# Battery_Holder_VNA.net
KiCad netlist of a schematic drawn in Altium Designer
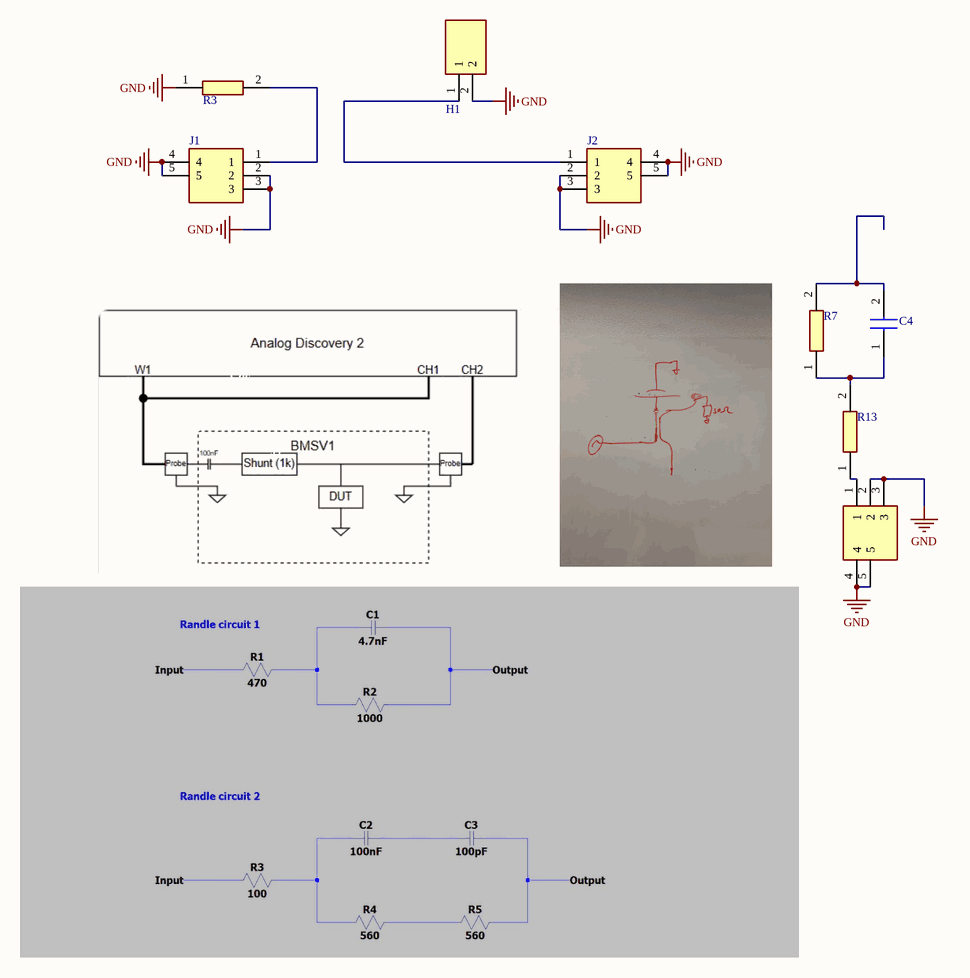
[diagram p0: Battery_Holder_VNA.SchDoc]

(export (version "E")
  (design (tool "Eeschema 10.0.6"))
  (components
    (comp (ref "C4")
      (value "200A472MT50XT")
      (footprint "SamacSys:CAPC1514X145N")
      (description "Capacitor")
      (libsource (lib "*") (part "200A472MT50XT"))
    )
    (comp (ref "H1")
      (value "1015")
      (footprint "SamacSys:1015")
      (description "Hardware")
      (fields (field (name "MOUSER PART NUMBER") "534-1015"))
      (libsource (lib "*") (part "1015"))
    )
    (comp (ref "J1")
      (value "60311002114501")
      (footprint "SamacSys:60311002114501")
      (description "Connector")
      (fields (field (name "MOUSER PART NUMBER") "710-60311002114501"))
      (libsource (lib "*") (part "60311002114501"))
    )
    (comp (ref "J2")
      (value "60311002114501")
      (footprint "SamacSys:60311002114501")
      (description "Connector")
      (fields (field (name "MOUSER PART NUMBER") "710-60311002114501"))
      (libsource (lib "") (part "60311002114501_2"))
    )
    (comp (ref "J3")
      (value "60311002114501")
      (footprint "SamacSys:60311002114501")
      (description "Connector")
      (fields (field (name "MOUSER PART NUMBER") "710-60311002114501"))
      (libsource (lib "") (part "60311002114501_1"))
    )
    (comp (ref "R3")
      (value "CH0402-50RGFT")
      (footprint "SamacSys:RESC1006X63N")
      (description "Resistor")
      (fields (field (name "MOUSER PART NUMBER") "71-CH0402-50RGFT"))
      (libsource (lib "*") (part "CH0402-50RGFT"))
    )
    (comp (ref "R7")
      (value "FC0402E1001DTT5")
      (footprint "SamacSys:RESC1106X42N")
      (description "Resistor")
      (fields (field (name "MOUSER PART NUMBER") "71-FC0402E1001DTT5"))
      (libsource (lib "*") (part "FC0402E1001DTT5"))
    )
    (comp (ref "R13")
      (value "CH0402-500RGFPT")
      (footprint "SamacSys:RESC1006X63N")
      (description "Resistor")
      (fields (field (name "MOUSER PART NUMBER") "71-CH0402-500RGFPT"))
      (libsource (lib "*") (part "CH0402-500RGFPT"))
    )
  )
  (nets
    (net (code "1") (name "GND") (class "Default")
      (node (ref "H1") (pin "2") (pinfunction "2_2") (pintype "passive"))
      (node (ref "J1") (pin "2") (pinfunction "2_2") (pintype "passive"))
      (node (ref "J1") (pin "3") (pinfunction "3_3") (pintype "passive"))
      (node (ref "J1") (pin "4") (pinfunction "4_4") (pintype "passive"))
      (node (ref "J1") (pin "5") (pinfunction "5_5") (pintype "passive"))
      (node (ref "J2") (pin "2") (pinfunction "2_2") (pintype "passive"))
      (node (ref "J2") (pin "3") (pinfunction "3_3") (pintype "passive"))
      (node (ref "J2") (pin "4") (pinfunction "4_4") (pintype "passive"))
      (node (ref "J2") (pin "5") (pinfunction "5_5") (pintype "passive"))
      (node (ref "J3") (pin "2") (pinfunction "2_2") (pintype "passive"))
      (node (ref "J3") (pin "3") (pinfunction "3_3") (pintype "passive"))
      (node (ref "J3") (pin "4") (pinfunction "4_4") (pintype "passive"))
      (node (ref "J3") (pin "5") (pinfunction "5_5") (pintype "passive"))
      (node (ref "R3") (pin "1") (pinfunction "1_1") (pintype "passive"))
    )
    (net (code "2") (name "Net-(C4-Pad1)") (class "Default")
      (node (ref "C4") (pin "1") (pinfunction "1_1") (pintype "passive"))
      (node (ref "R13") (pin "2") (pinfunction "2_2") (pintype "passive"))
      (node (ref "R7") (pin "1") (pinfunction "1_1") (pintype "passive"))
    )
    (net (code "3") (name "Net-(C4-Pad2)") (class "Default")
      (node (ref "C4") (pin "2") (pinfunction "2_2") (pintype "passive"))
      (node (ref "R7") (pin "2") (pinfunction "2_2") (pintype "passive"))
    )
    (net (code "4") (name "Net-(H1-Pad1)") (class "Default")
      (node (ref "H1") (pin "1") (pinfunction "1_1") (pintype "passive"))
      (node (ref "J2") (pin "1") (pinfunction "1_1") (pintype "passive"))
    )
    (net (code "5") (name "Net-(J1-Pad1)") (class "Default")
      (node (ref "J1") (pin "1") (pinfunction "1_1") (pintype "passive"))
      (node (ref "R3") (pin "2") (pinfunction "2_2") (pintype "passive"))
    )
    (net (code "6") (name "Net-(J3-Pad1)") (class "Default")
      (node (ref "J3") (pin "1") (pinfunction "1_1") (pintype "passive"))
      (node (ref "R13") (pin "1") (pinfunction "1_1") (pintype "passive"))
    )
  )
)
